# clock.net
KiCad netlist of a schematic drawn in EAGLE
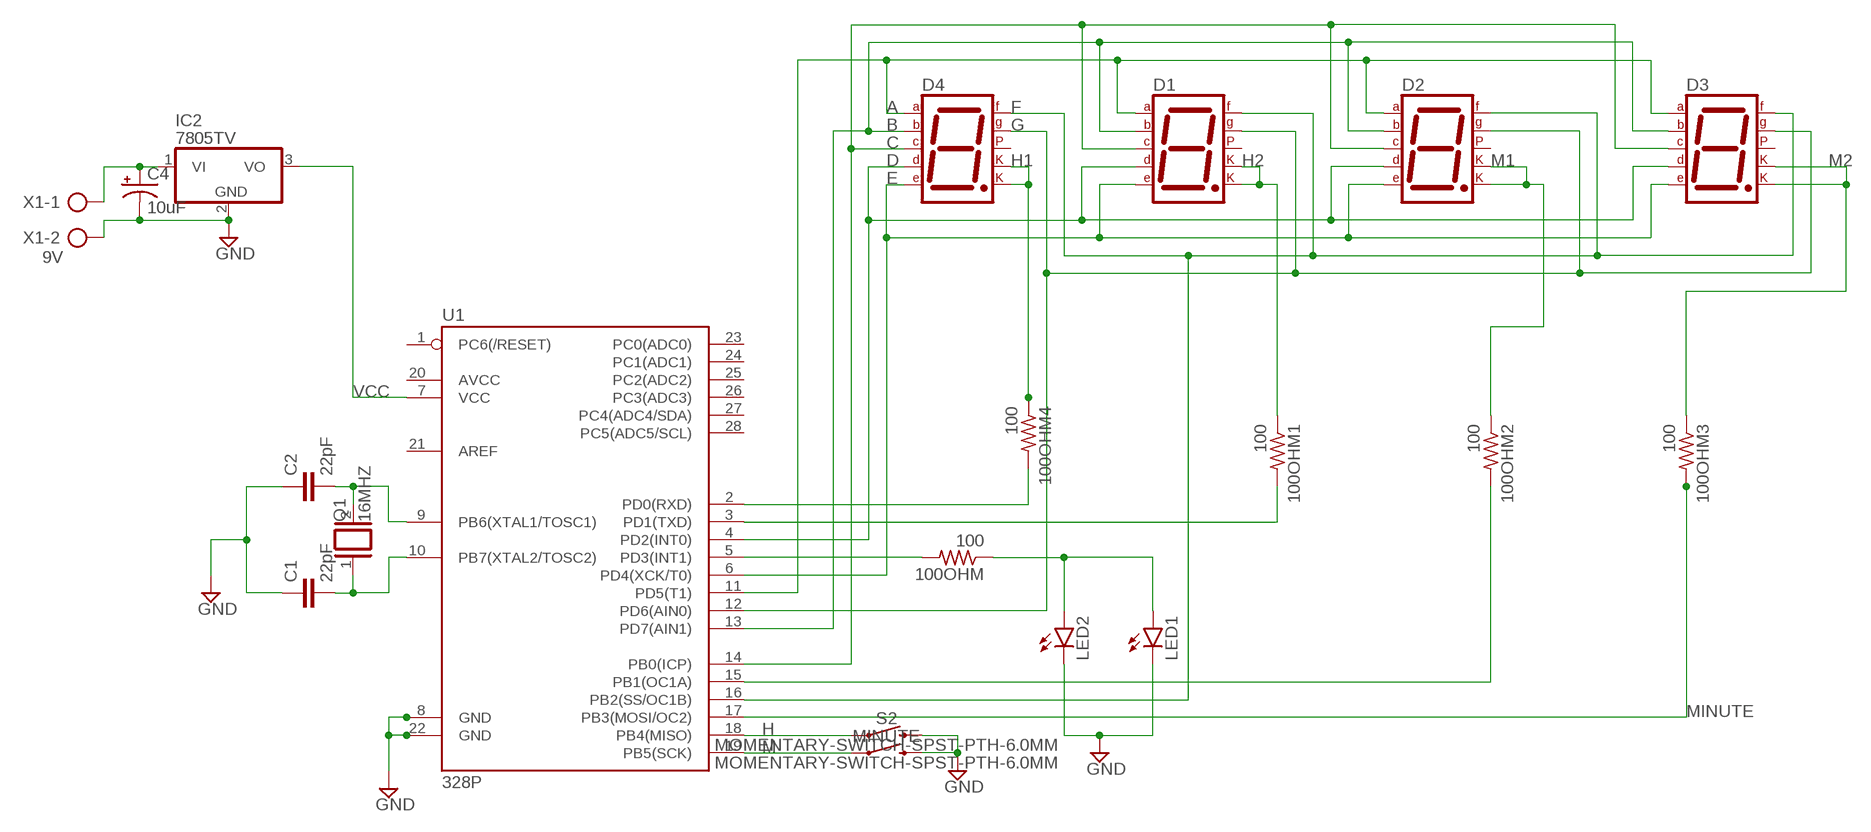
[diagram p0: schematic, sheet 1]

(export (version "E")
  (design (tool "Eeschema 10.0.6"))
  (components
    (comp (ref "100OHM")
      (value "100")
      (footprint "eagle-import:0207_10")
      (libsource (lib "eagle-import") (part "R-US_0207/10"))
    )
    (comp (ref "100OHM1")
      (value "100")
      (footprint "eagle-import:0207_10")
      (libsource (lib "eagle-import") (part "R-US_0207/10"))
    )
    (comp (ref "100OHM2")
      (value "100")
      (footprint "eagle-import:0207_10")
      (libsource (lib "eagle-import") (part "R-US_0207/10"))
    )
    (comp (ref "100OHM3")
      (value "100")
      (footprint "eagle-import:0207_10")
      (libsource (lib "eagle-import") (part "R-US_0207/10"))
    )
    (comp (ref "100OHM4")
      (value "100")
      (footprint "eagle-import:0207_10")
      (libsource (lib "eagle-import") (part "R-US_0207/10"))
    )
    (comp (ref "C1")
      (value "22pF")
      (footprint "eagle-import:CAP-PTH-2.54")
      (libsource (lib "eagle-import") (part "22PF-PTH-2.54MM-200V-5%"))
    )
    (comp (ref "C2")
      (value "22pF")
      (footprint "eagle-import:CAP-PTH-2.54")
      (libsource (lib "eagle-import") (part "22PF-PTH-2.54MM-200V-5%"))
    )
    (comp (ref "C4")
      (value "10uF")
      (footprint "eagle-import:CPOL-RADIAL-2.5MM-5MM")
      (libsource (lib "eagle-import") (part "10UF-POLAR-RADIAL-2.5MM-25V-20%"))
    )
    (comp (ref "D1")
      (value "7SEG-CK")
      (footprint "eagle-import:7SEG-13")
      (libsource (lib "eagle-import") (part "7SEG-CK"))
    )
    (comp (ref "D2")
      (value "7SEG-CK")
      (footprint "eagle-import:7SEG-13")
      (libsource (lib "eagle-import") (part "7SEG-CK"))
    )
    (comp (ref "D3")
      (value "7SEG-CK")
      (footprint "eagle-import:7SEG-13")
      (libsource (lib "eagle-import") (part "7SEG-CK"))
    )
    (comp (ref "D4")
      (value "7SEG-CK")
      (footprint "eagle-import:7SEG-13")
      (libsource (lib "eagle-import") (part "7SEG-CK"))
    )
    (comp (ref "IC2")
      (value "7805TV")
      (footprint "eagle-import:TO220V")
      (libsource (lib "eagle-import") (part "78TV05"))
    )
    (comp (ref "LED1")
      (value "LED5MM")
      (footprint "eagle-import:LED5MM")
      (libsource (lib "eagle-import") (part "LED5MM"))
    )
    (comp (ref "LED2")
      (value "LED5MM")
      (footprint "eagle-import:LED5MM")
      (libsource (lib "eagle-import") (part "LED5MM"))
    )
    (comp (ref "MINUTE")
      (value "MOMENTARY-SWITCH-SPST-PTH-6.0MM")
      (footprint "eagle-import:TACTILE_SWITCH_PTH_6.0MM")
      (libsource (lib "eagle-import") (part "MOMENTARY-SWITCH-SPST-PTH-6.0MM"))
    )
    (comp (ref "Q1")
      (value "16MHZ")
      (footprint "eagle-import:QS")
      (libsource (lib "eagle-import") (part "XTAL/S"))
    )
    (comp (ref "S2")
      (value "MOMENTARY-SWITCH-SPST-PTH-6.0MM")
      (footprint "eagle-import:TACTILE_SWITCH_PTH_6.0MM")
      (libsource (lib "eagle-import") (part "MOMENTARY-SWITCH-SPST-PTH-6.0MM"))
    )
    (comp (ref "U1")
      (value "328P")
      (footprint "eagle-import:DIP28")
      (libsource (lib "eagle-import") (part "ATMEGA328P_PDIP"))
    )
    (comp (ref "X1")
      (value "9V")
      (footprint "eagle-import:AK500_2-H")
      (libsource (lib "eagle-import") (part "AK500/2-H"))
    )
  )
  (nets
    (net (code "1") (name "/A") (class "Default")
      (node (ref "D1") (pin "7") (pinfunction "A_7") (pintype "passive"))
      (node (ref "D2") (pin "7") (pinfunction "A_7") (pintype "passive"))
      (node (ref "D3") (pin "7") (pinfunction "A_7") (pintype "passive"))
      (node (ref "D4") (pin "7") (pinfunction "A_7") (pintype "passive"))
      (node (ref "U1") (pin "11") (pinfunction "PD5(T1)_11") (pintype "bidirectional"))
    )
    (net (code "2") (name "/B") (class "Default")
      (node (ref "D1") (pin "6") (pinfunction "B_6") (pintype "passive"))
      (node (ref "D2") (pin "6") (pinfunction "B_6") (pintype "passive"))
      (node (ref "D3") (pin "6") (pinfunction "B_6") (pintype "passive"))
      (node (ref "D4") (pin "6") (pinfunction "B_6") (pintype "passive"))
      (node (ref "U1") (pin "13") (pinfunction "PD7(AIN1)_13") (pintype "bidirectional"))
    )
    (net (code "3") (name "/C") (class "Default")
      (node (ref "D1") (pin "4") (pinfunction "C_4") (pintype "passive"))
      (node (ref "D2") (pin "4") (pinfunction "C_4") (pintype "passive"))
      (node (ref "D3") (pin "4") (pinfunction "C_4") (pintype "passive"))
      (node (ref "D4") (pin "4") (pinfunction "C_4") (pintype "passive"))
      (node (ref "U1") (pin "14") (pinfunction "PB0(ICP)_14") (pintype "bidirectional"))
    )
    (net (code "4") (name "/D") (class "Default")
      (node (ref "D1") (pin "2") (pinfunction "D_2") (pintype "passive"))
      (node (ref "D2") (pin "2") (pinfunction "D_2") (pintype "passive"))
      (node (ref "D3") (pin "2") (pinfunction "D_2") (pintype "passive"))
      (node (ref "D4") (pin "2") (pinfunction "D_2") (pintype "passive"))
      (node (ref "U1") (pin "4") (pinfunction "PD2(INT0)_4") (pintype "bidirectional"))
    )
    (net (code "5") (name "/E") (class "Default")
      (node (ref "D1") (pin "1") (pinfunction "E_1") (pintype "passive"))
      (node (ref "D2") (pin "1") (pinfunction "E_1") (pintype "passive"))
      (node (ref "D3") (pin "1") (pinfunction "E_1") (pintype "passive"))
      (node (ref "D4") (pin "1") (pinfunction "E_1") (pintype "passive"))
      (node (ref "U1") (pin "6") (pinfunction "PD4(XCK/T0)_6") (pintype "bidirectional"))
    )
    (net (code "6") (name "/F") (class "Default")
      (node (ref "D1") (pin "9") (pinfunction "F_9") (pintype "passive"))
      (node (ref "D2") (pin "9") (pinfunction "F_9") (pintype "passive"))
      (node (ref "D3") (pin "9") (pinfunction "F_9") (pintype "passive"))
      (node (ref "D4") (pin "9") (pinfunction "F_9") (pintype "passive"))
      (node (ref "U1") (pin "16") (pinfunction "PB2(SS/OC1B)_16") (pintype "bidirectional"))
    )
    (net (code "7") (name "/G") (class "Default")
      (node (ref "D1") (pin "10") (pinfunction "G_10") (pintype "passive"))
      (node (ref "D2") (pin "10") (pinfunction "G_10") (pintype "passive"))
      (node (ref "D3") (pin "10") (pinfunction "G_10") (pintype "passive"))
      (node (ref "D4") (pin "10") (pinfunction "G_10") (pintype "passive"))
      (node (ref "U1") (pin "12") (pinfunction "PD6(AIN0)_12") (pintype "bidirectional"))
    )
    (net (code "8") (name "/H") (class "Default")
      (node (ref "S2") (pin "1") (pinfunction "1_1") (pintype "passive"))
      (node (ref "U1") (pin "18") (pinfunction "PB4(MISO)_18") (pintype "bidirectional"))
    )
    (net (code "9") (name "/H1") (class "Default")
      (node (ref "100OHM4") (pin "1") (pinfunction "1_1") (pintype "passive"))
      (node (ref "D4") (pin "3") (pinfunction "CK1_3") (pintype "passive"))
      (node (ref "D4") (pin "8") (pinfunction "CK2_8") (pintype "passive"))
    )
    (net (code "10") (name "/H2") (class "Default")
      (node (ref "100OHM1") (pin "1") (pinfunction "1_1") (pintype "passive"))
      (node (ref "D1") (pin "3") (pinfunction "CK1_3") (pintype "passive"))
      (node (ref "D1") (pin "8") (pinfunction "CK2_8") (pintype "passive"))
    )
    (net (code "11") (name "/M") (class "Default")
      (node (ref "MINUTE") (pin "1") (pinfunction "1_1") (pintype "passive"))
      (node (ref "U1") (pin "19") (pinfunction "PB5(SCK)_19") (pintype "bidirectional"))
    )
    (net (code "12") (name "/M1") (class "Default")
      (node (ref "100OHM2") (pin "1") (pinfunction "1_1") (pintype "passive"))
      (node (ref "D2") (pin "3") (pinfunction "CK1_3") (pintype "passive"))
      (node (ref "D2") (pin "8") (pinfunction "CK2_8") (pintype "passive"))
    )
    (net (code "13") (name "/M2") (class "Default")
      (node (ref "100OHM3") (pin "1") (pinfunction "1_1") (pintype "passive"))
      (node (ref "D3") (pin "3") (pinfunction "CK1_3") (pintype "passive"))
      (node (ref "D3") (pin "8") (pinfunction "CK2_8") (pintype "passive"))
    )
    (net (code "14") (name "/MINUTE") (class "Default")
      (node (ref "100OHM3") (pin "2") (pinfunction "2_2") (pintype "passive"))
      (node (ref "U1") (pin "17") (pinfunction "PB3(MOSI/OC2)_17") (pintype "bidirectional"))
    )
    (net (code "15") (name "/VCC") (class "Default")
      (node (ref "IC2") (pin "3") (pinfunction "VO_3") (pintype "passive"))
      (node (ref "U1") (pin "7") (pinfunction "VCC_7") (pintype "bidirectional"))
    )
    (net (code "16") (name "GND") (class "Default")
      (node (ref "C1") (pin "1") (pinfunction "1_1") (pintype "passive"))
      (node (ref "C2") (pin "1") (pinfunction "1_1") (pintype "passive"))
      (node (ref "C4") (pin "2") (pinfunction "-_2") (pintype "passive"))
      (node (ref "IC2") (pin "2") (pinfunction "GND_2") (pintype "passive"))
      (node (ref "LED1") (pin "K") (pinfunction "C_K") (pintype "passive"))
      (node (ref "LED2") (pin "K") (pinfunction "C_K") (pintype "passive"))
      (node (ref "MINUTE") (pin "3") (pinfunction "2_3") (pintype "passive"))
      (node (ref "S2") (pin "3") (pinfunction "2_3") (pintype "passive"))
      (node (ref "U1") (pin "22") (pinfunction "GND_22") (pintype "bidirectional"))
      (node (ref "U1") (pin "8") (pinfunction "GND_8") (pintype "bidirectional"))
      (node (ref "X1") (pin "2") (pinfunction "KL_2") (pintype "passive"))
    )
    (net (code "17") (name "Net-(100OHM-Pad1)") (class "Default")
      (node (ref "100OHM") (pin "1") (pinfunction "1_1") (pintype "passive"))
      (node (ref "LED1") (pin "A") (pinfunction "A_A") (pintype "passive"))
      (node (ref "LED2") (pin "A") (pinfunction "A_A") (pintype "passive"))
    )
    (net (code "18") (name "Net-(C4-+)") (class "Default")
      (node (ref "C4") (pin "1") (pinfunction "+_1") (pintype "passive"))
      (node (ref "IC2") (pin "1") (pinfunction "VI_1") (pintype "input"))
      (node (ref "X1") (pin "1") (pinfunction "KL_1") (pintype "passive"))
    )
    (net (code "19") (name "Net-(U1-PB1(OC1A))") (class "Default")
      (node (ref "100OHM2") (pin "2") (pinfunction "2_2") (pintype "passive"))
      (node (ref "U1") (pin "15") (pinfunction "PB1(OC1A)_15") (pintype "bidirectional"))
    )
    (net (code "20") (name "Net-(U1-PB6(XTAL1{slash}TOSC1))") (class "Default")
      (node (ref "C2") (pin "2") (pinfunction "2_2") (pintype "passive"))
      (node (ref "Q1") (pin "2") (pinfunction "2_2") (pintype "passive"))
      (node (ref "U1") (pin "9") (pinfunction "PB6(XTAL1/TOSC1)_9") (pintype "bidirectional"))
    )
    (net (code "21") (name "Net-(U1-PB7(XTAL2{slash}TOSC2))") (class "Default")
      (node (ref "C1") (pin "2") (pinfunction "2_2") (pintype "passive"))
      (node (ref "Q1") (pin "1") (pinfunction "1_1") (pintype "passive"))
      (node (ref "U1") (pin "10") (pinfunction "PB7(XTAL2/TOSC2)_10") (pintype "bidirectional"))
    )
    (net (code "22") (name "Net-(U1-PD0(RXD))") (class "Default")
      (node (ref "100OHM4") (pin "2") (pinfunction "2_2") (pintype "passive"))
      (node (ref "U1") (pin "2") (pinfunction "PD0(RXD)_2") (pintype "bidirectional"))
    )
    (net (code "23") (name "Net-(U1-PD1(TXD))") (class "Default")
      (node (ref "100OHM1") (pin "2") (pinfunction "2_2") (pintype "passive"))
      (node (ref "U1") (pin "3") (pinfunction "PD1(TXD)_3") (pintype "bidirectional"))
    )
    (net (code "24") (name "Net-(U1-PD3(INT1))") (class "Default")
      (node (ref "100OHM") (pin "2") (pinfunction "2_2") (pintype "passive"))
      (node (ref "U1") (pin "5") (pinfunction "PD3(INT1)_5") (pintype "bidirectional"))
    )
    (net (code "25") (name "unconnected-(D1-DP-Pad5)") (class "Default")
      (node (ref "D1") (pin "5") (pinfunction "DP_5") (pintype "passive"))
    )
    (net (code "26") (name "unconnected-(D2-DP-Pad5)") (class "Default")
      (node (ref "D2") (pin "5") (pinfunction "DP_5") (pintype "passive"))
    )
    (net (code "27") (name "unconnected-(D3-DP-Pad5)") (class "Default")
      (node (ref "D3") (pin "5") (pinfunction "DP_5") (pintype "passive"))
    )
    (net (code "28") (name "unconnected-(D4-DP-Pad5)") (class "Default")
      (node (ref "D4") (pin "5") (pinfunction "DP_5") (pintype "passive"))
    )
    (net (code "29") (name "unconnected-(U1-AREF-Pad21)") (class "Default")
      (node (ref "U1") (pin "21") (pinfunction "AREF_21") (pintype "bidirectional"))
    )
    (net (code "30") (name "unconnected-(U1-AVCC-Pad20)") (class "Default")
      (node (ref "U1") (pin "20") (pinfunction "AVCC_20") (pintype "bidirectional"))
    )
    (net (code "31") (name "unconnected-(U1-PC0(ADC0)-Pad23)") (class "Default")
      (node (ref "U1") (pin "23") (pinfunction "PC0(ADC0)_23") (pintype "bidirectional"))
    )
    (net (code "32") (name "unconnected-(U1-PC1(ADC1)-Pad24)") (class "Default")
      (node (ref "U1") (pin "24") (pinfunction "PC1(ADC1)_24") (pintype "bidirectional"))
    )
    (net (code "33") (name "unconnected-(U1-PC2(ADC2)-Pad25)") (class "Default")
      (node (ref "U1") (pin "25") (pinfunction "PC2(ADC2)_25") (pintype "bidirectional"))
    )
    (net (code "34") (name "unconnected-(U1-PC3(ADC3)-Pad26)") (class "Default")
      (node (ref "U1") (pin "26") (pinfunction "PC3(ADC3)_26") (pintype "bidirectional"))
    )
    (net (code "35") (name "unconnected-(U1-PC4(ADC4{slash}SDA)-Pad27)") (class "Default")
      (node (ref "U1") (pin "27") (pinfunction "PC4(ADC4/SDA)_27") (pintype "bidirectional"))
    )
    (net (code "36") (name "unconnected-(U1-PC5(ADC5{slash}SCL)-Pad28)") (class "Default")
      (node (ref "U1") (pin "28") (pinfunction "PC5(ADC5/SCL)_28") (pintype "bidirectional"))
    )
    (net (code "37") (name "unconnected-(U1-PC6({slash}RESET)-Pad1)") (class "Default")
      (node (ref "U1") (pin "1") (pinfunction "PC6(/RESET)_1") (pintype "bidirectional"))
    )
  )
)
